# MCU.net
KiCad netlist of a schematic drawn in Altium Designer
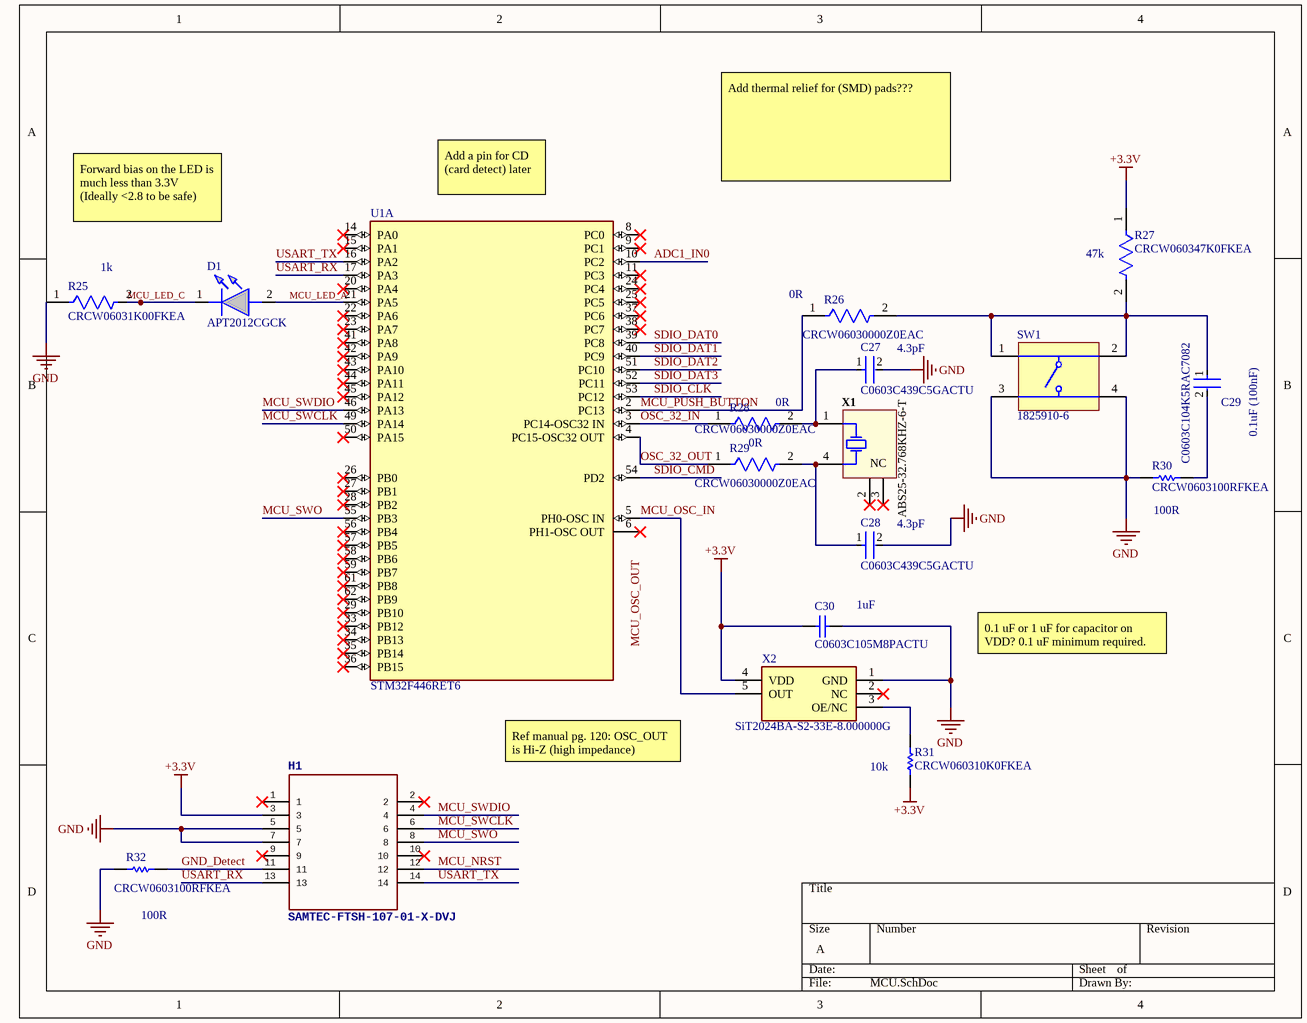
[diagram p0: MCU.SchDoc]

(export (version "E")
  (design (tool "Eeschema 10.0.6"))
  (components
    (comp (ref "C27")
      (value "C0603C439C5GACTU")
      (footprint "FP-C0603C-CF-MFG")
      (description "CAP CER 4.3PF 50V NP0 0603")
      (fields
        (field (name "OCTOPART") "https://octopart.com/c0603c439c5gactu-kemet-8375741")
        (field (name "TOLERANCE") "0.25 pF")
      )
      (libsource (lib "Altium Content Vault") (part "b4654b650e69147ec39a6b967a45e02"))
    )
    (comp (ref "C28")
      (value "C0603C439C5GACTU")
      (footprint "FP-C0603C-CF-MFG")
      (description "CAP CER 4.3PF 50V NP0 0603")
      (fields
        (field (name "OCTOPART") "https://octopart.com/c0603c439c5gactu-kemet-8375741")
        (field (name "TOLERANCE") "0.25 pF")
      )
      (libsource (lib "Altium Content Vault") (part "b4654b650e69147ec39a6b967a45e02"))
    )
    (comp (ref "C29")
      (value "C0603C104K5RAC7082")
      (footprint "FP-C0603C-CF-MFG")
      (description "C0603 0.10 μF X7R 30ppm/°C 10.00% 50 V")
      (fields
        (field (name "OCTOPART") "https://octopart.com/c0603c104k5rac7082-kemet-75146597")
        (field (name "MANUFACTURER") "KEMET")
      )
      (libsource (lib "Altium Content Vault") (part "b4654b650e69147ec39a6b967a45e02"))
    )
    (comp (ref "C30")
      (value "C0603C105M8PACTU")
      (footprint "CAPC1608X90X35LL15T15")
      (fields (field (name "MANUFACTURER") "Kemet"))
      (libsource (lib "Altium Content Vault") (part "CAP"))
    )
    (comp (ref "D1")
      (value "APT2012CGCK")
      (footprint "LEDC2012X50N")
      (fields (field (name "MOUSER PART NUMBER") "604-APT2012CGCK"))
      (libsource (lib "APT2012CGCK") (part "APT2012CGCK"))
    )
    (comp (ref "H1")
      (value "SAMTEC-FTSH-107-01-X-DVJ")
      (footprint "SAMTEC_FTSH-107-01-F-DV-K-P-TR")
      (libsource (lib "SAMTEC-FTSH-107-01-X-DV") (part "SAMTEC-FTSH-107-01-X-DVJ"))
    )
    (comp (ref "R25")
      (value "CRCW06031K00FKEA")
      (footprint "FP-CRCW0603-e3-MFG")
      (description "RES Thick Film, 1kΩ, 1%, 0.1W, 100ppm/°C, 0603")
      (fields (field (name "TOLERANCE") "1%"))
      (libsource (lib "Altium Content Vault") (part "1029c3af85768c4190bb7ad29bc67b5"))
    )
    (comp (ref "R26")
      (value "CRCW06030000Z0EAC")
      (footprint "FP-CRCW0603-C-IPC_B")
      (description "RES 0 OHM JUMPER 1/10W 0603")
      (libsource (lib "Altium Content Vault") (part "1029c3af85768c4190bb7ad29bc67b5"))
    )
    (comp (ref "R27")
      (value "CRCW060347K0FKEA")
      (footprint "FP-CRCW0603-e3-IPC_B")
      (description "RES SMD 47K OHM 1% 1/10W 0603")
      (fields (field (name "TOLERANCE") "1%"))
      (libsource (lib "Altium Content Vault") (part "1029c3af85768c4190bb7ad29bc67b5"))
    )
    (comp (ref "R28")
      (value "CRCW06030000Z0EAC")
      (footprint "FP-CRCW0603-C-IPC_B")
      (description "RES 0 OHM JUMPER 1/10W 0603")
      (libsource (lib "Altium Content Vault") (part "1029c3af85768c4190bb7ad29bc67b5"))
    )
    (comp (ref "R29")
      (value "CRCW06030000Z0EAC")
      (footprint "FP-CRCW0603-C-IPC_B")
      (description "RES 0 OHM JUMPER 1/10W 0603")
      (libsource (lib "Altium Content Vault") (part "1029c3af85768c4190bb7ad29bc67b5"))
    )
    (comp (ref "R30")
      (value "CRCW0603100RFKEA")
      (footprint "RESC1609X50X30ML8T20")
      (description "Chip Resistor, 100 Ohm, +/- 1%, 100 mW,-55 to 155 degC, 0603 (1608 Metric), RoHS, Tape and Ree")
      (fields (field (name "MANUFACTURER") "Vishay Semiconductor"))
      (libsource (lib "Altium Content Vault") (part "RES-2"))
    )
    (comp (ref "R31")
      (value "CRCW060310K0FKEA")
      (footprint "RESC1609X50X30NL8T20")
      (description "Chip Resistor, 10 KOhm, +/- 1%, 100 mW, -55 to 155 degC, 0603 (1608 Metric), RoHS, Tape and Reel")
      (fields (field (name "MANUFACTURER") "Vishay Semiconductor"))
      (libsource (lib "Altium Content Vault") (part "RES-2"))
    )
    (comp (ref "R32")
      (value "CRCW0603100RFKEA")
      (footprint "RESC1609X50X30ML8T20")
      (description "Chip Resistor, 100 Ohm, +/- 1%, 100 mW,-55 to 155 degC, 0603 (1608 Metric), RoHS, Tape and Ree")
      (fields (field (name "MANUFACTURER") "Vishay Semiconductor"))
      (libsource (lib "Altium Content Vault") (part "RES-2"))
    )
    (comp (ref "SW1")
      (value "1825910-6")
      (footprint "TECO-1825910-6_V")
      (description "Tact Switch, SPST-NO, 0.05 A, -35 to 85 degC, 4-Pin THD, RoHS, Bulk")
      (fields (field (name "MANUFACTURER") "TE Connectivity"))
      (libsource (lib "Altium Content Vault") (part "SW-SPST-4_A"))
    )
    (comp (ref "U1")
      (value "STM32F446RET6")
      (footprint "FP-LQFP64-5W-MFG")
      (description "IC MCU 32BIT 512KB FLASH 64LQFP")
      (fields
        (field (name "OCTOPART") "https://octopart.com/stm32f446ret6-stmicroelectronics-52642920")
        (field (name "MANUFACTURER") "ST")
      )
      (libsource (lib "Altium Content Vault") (part "ee11adc32c0ab33b933cccf4348c338"))
    )
    (comp (ref "X1")
      (value "ABS25-32.768KHZ-6-T")
      (footprint "ABRA-ABS25-4_V")
      (fields (field (name "TOLERANCE") "20PPM") (field (name "MANUFACTURER") "Abracon"))
      (libsource (lib "Altium Content Vault") (part "ABRA-XTAL_1-4-4"))
    )
    (comp (ref "X2")
      (value "SiT2024BA-S2-33E-8.000000G")
      (footprint "SOT95P280X145-5N")
      (description "Standard Clock Oscillators 8MHz 3.3V -40C +125C AEC-Q100")
      (fields (field (name "MOUSER PART NUMBER") "788-2024BA-S2-33E-8G"))
      (libsource (lib "SiT2024BA-S2-33E-8.000000G") (part "SiT2024BA-S2-33E-8.000000G"))
    )
  )
  (nets
    (net (code "1") (name "+3.3V") (class "Default")
      (node (ref "C30") (pin "1") (pinfunction "1_1") (pintype "passive"))
      (node (ref "H1") (pin "3") (pinfunction "3_3") (pintype "passive"))
      (node (ref "R27") (pin "1") (pinfunction "1_1") (pintype "passive"))
      (node (ref "R31") (pin "2") (pinfunction "2_2") (pintype "passive"))
      (node (ref "X2") (pin "4") (pinfunction "VDD_4") (pintype "power_in"))
    )
    (net (code "2") (name "/ADC1_IN0") (class "Default")
      (node (ref "U1") (pin "10") (pinfunction "PC2_10") (pintype "bidirectional"))
    )
    (net (code "3") (name "/GND_Detect") (class "Default")
      (node (ref "H1") (pin "11") (pinfunction "11_11") (pintype "passive"))
      (node (ref "R32") (pin "1") (pinfunction "1_1") (pintype "passive"))
    )
    (net (code "4") (name "/MCU_LED_A") (class "Default")
      (node (ref "D1") (pin "2") (pinfunction "A_2") (pintype "passive"))
      (node (ref "U1") (pin "21") (pinfunction "PA5_21") (pintype "bidirectional"))
    )
    (net (code "5") (name "/MCU_LED_C") (class "Default")
      (node (ref "D1") (pin "1") (pinfunction "K_1") (pintype "passive"))
      (node (ref "R25") (pin "2") (pinfunction "2_2") (pintype "passive"))
    )
    (net (code "6") (name "/MCU_NRST") (class "Default")
      (node (ref "H1") (pin "12") (pinfunction "12_12") (pintype "passive"))
    )
    (net (code "7") (name "/MCU_OSC_IN") (class "Default")
      (node (ref "U1") (pin "5") (pinfunction "PH0-OSC_IN_5") (pintype "bidirectional"))
      (node (ref "X2") (pin "5") (pinfunction "OUT_5") (pintype "passive"))
    )
    (net (code "9") (name "/MCU_PUSH_BUTTON") (class "Default")
      (node (ref "R26") (pin "1") (pinfunction "1_1") (pintype "passive"))
      (node (ref "U1") (pin "2") (pinfunction "PC13_2") (pintype "bidirectional"))
    )
    (net (code "10") (name "/MCU_SWCLK") (class "Default")
      (node (ref "H1") (pin "6") (pinfunction "6_6") (pintype "passive"))
      (node (ref "U1") (pin "49") (pinfunction "PA14_49") (pintype "bidirectional"))
    )
    (net (code "11") (name "/MCU_SWDIO") (class "Default")
      (node (ref "H1") (pin "4") (pinfunction "4_4") (pintype "passive"))
      (node (ref "U1") (pin "46") (pinfunction "PA13_46") (pintype "bidirectional"))
    )
    (net (code "12") (name "/MCU_SWO") (class "Default")
      (node (ref "H1") (pin "8") (pinfunction "8_8") (pintype "passive"))
      (node (ref "U1") (pin "55") (pinfunction "PB3_55") (pintype "bidirectional"))
    )
    (net (code "13") (name "/OSC_32_IN") (class "Default")
      (node (ref "R28") (pin "1") (pinfunction "1_1") (pintype "passive"))
      (node (ref "U1") (pin "3") (pinfunction "PC14-OSC32_IN_3") (pintype "bidirectional"))
    )
    (net (code "14") (name "/OSC_32_OUT") (class "Default")
      (node (ref "R29") (pin "1") (pinfunction "1_1") (pintype "passive"))
      (node (ref "U1") (pin "4") (pinfunction "PC15-OSC32_OUT_4") (pintype "bidirectional"))
    )
    (net (code "15") (name "/SDIO_CLK") (class "Default")
      (node (ref "U1") (pin "53") (pinfunction "PC12_53") (pintype "bidirectional"))
    )
    (net (code "16") (name "/SDIO_CMD") (class "Default")
      (node (ref "U1") (pin "54") (pinfunction "PD2_54") (pintype "bidirectional"))
    )
    (net (code "17") (name "/SDIO_DAT0") (class "Default")
      (node (ref "U1") (pin "39") (pinfunction "PC8_39") (pintype "bidirectional"))
    )
    (net (code "18") (name "/SDIO_DAT1") (class "Default")
      (node (ref "U1") (pin "40") (pinfunction "PC9_40") (pintype "bidirectional"))
    )
    (net (code "19") (name "/SDIO_DAT2") (class "Default")
      (node (ref "U1") (pin "51") (pinfunction "PC10_51") (pintype "bidirectional"))
    )
    (net (code "20") (name "/SDIO_DAT3") (class "Default")
      (node (ref "U1") (pin "52") (pinfunction "PC11_52") (pintype "bidirectional"))
    )
    (net (code "21") (name "/USART_RX") (class "Default")
      (node (ref "H1") (pin "13") (pinfunction "13_13") (pintype "passive"))
      (node (ref "U1") (pin "17") (pinfunction "PA3_17") (pintype "bidirectional"))
    )
    (net (code "22") (name "/USART_TX") (class "Default")
      (node (ref "H1") (pin "14") (pinfunction "14_14") (pintype "passive"))
      (node (ref "U1") (pin "16") (pinfunction "PA2_16") (pintype "bidirectional"))
    )
    (net (code "23") (name "GND") (class "Default")
      (node (ref "C27") (pin "2") (pinfunction "2_2") (pintype "passive"))
      (node (ref "C28") (pin "2") (pinfunction "2_2") (pintype "passive"))
      (node (ref "C30") (pin "2") (pinfunction "2_2") (pintype "passive"))
      (node (ref "H1") (pin "5") (pinfunction "5_5") (pintype "passive"))
      (node (ref "H1") (pin "7") (pinfunction "7_7") (pintype "passive"))
      (node (ref "R25") (pin "1") (pinfunction "1_1") (pintype "passive"))
      (node (ref "R30") (pin "2") (pinfunction "2_2") (pintype "passive"))
      (node (ref "R32") (pin "2") (pinfunction "2_2") (pintype "passive"))
      (node (ref "SW1") (pin "3") (pinfunction "3_3") (pintype "passive"))
      (node (ref "SW1") (pin "4") (pinfunction "4_4") (pintype "passive"))
      (node (ref "X2") (pin "1") (pinfunction "GND_1") (pintype "passive"))
    )
    (net (code "24") (name "Net-(C29-Pad1)") (class "Default")
      (node (ref "C29") (pin "1") (pinfunction "1_1") (pintype "passive"))
      (node (ref "R26") (pin "2") (pinfunction "2_2") (pintype "passive"))
      (node (ref "R27") (pin "2") (pinfunction "2_2") (pintype "passive"))
      (node (ref "SW1") (pin "1") (pinfunction "1_1") (pintype "passive"))
      (node (ref "SW1") (pin "2") (pinfunction "2_2") (pintype "passive"))
    )
    (net (code "25") (name "Net-(C29-Pad2)") (class "Default")
      (node (ref "C29") (pin "2") (pinfunction "2_2") (pintype "passive"))
      (node (ref "R30") (pin "1") (pinfunction "1_1") (pintype "passive"))
    )
    (net (code "26") (name "Net-(X1-X1)") (class "Default")
      (node (ref "C27") (pin "1") (pinfunction "1_1") (pintype "passive"))
      (node (ref "R28") (pin "2") (pinfunction "2_2") (pintype "passive"))
      (node (ref "X1") (pin "1") (pinfunction "X1_1") (pintype "passive"))
    )
    (net (code "27") (name "Net-(X1-X2)") (class "Default")
      (node (ref "C28") (pin "1") (pinfunction "1_1") (pintype "passive"))
      (node (ref "R29") (pin "2") (pinfunction "2_2") (pintype "passive"))
      (node (ref "X1") (pin "4") (pinfunction "X2_4") (pintype "passive"))
    )
    (net (code "28") (name "Net-(X2-OE{slash}NC)") (class "Default")
      (node (ref "R31") (pin "1") (pinfunction "1_1") (pintype "passive"))
      (node (ref "X2") (pin "3") (pinfunction "OE/NC_3") (pintype "passive"))
    )
    (net (code "29") (name "unconnected-(H1-Pad1)") (class "Default")
      (node (ref "H1") (pin "1") (pinfunction "1_1") (pintype "passive+no_connect"))
    )
    (net (code "30") (name "unconnected-(H1-Pad2)") (class "Default")
      (node (ref "H1") (pin "2") (pinfunction "2_2") (pintype "passive+no_connect"))
    )
    (net (code "31") (name "unconnected-(H1-Pad9)") (class "Default")
      (node (ref "H1") (pin "9") (pinfunction "9_9") (pintype "passive+no_connect"))
    )
    (net (code "32") (name "unconnected-(H1-Pad10)") (class "Default")
      (node (ref "H1") (pin "10") (pinfunction "10_10") (pintype "passive+no_connect"))
    )
    (net (code "33") (name "unconnected-(U1A-PA0-Pad14)") (class "Default")
      (node (ref "U1") (pin "14") (pinfunction "PA0_14") (pintype "bidirectional+no_connect"))
    )
    (net (code "34") (name "unconnected-(U1A-PA1-Pad15)") (class "Default")
      (node (ref "U1") (pin "15") (pinfunction "PA1_15") (pintype "bidirectional+no_connect"))
    )
    (net (code "35") (name "unconnected-(U1A-PA4-Pad20)") (class "Default")
      (node (ref "U1") (pin "20") (pinfunction "PA4_20") (pintype "bidirectional+no_connect"))
    )
    (net (code "36") (name "unconnected-(U1A-PA6-Pad22)") (class "Default")
      (node (ref "U1") (pin "22") (pinfunction "PA6_22") (pintype "bidirectional+no_connect"))
    )
    (net (code "37") (name "unconnected-(U1A-PA7-Pad23)") (class "Default")
      (node (ref "U1") (pin "23") (pinfunction "PA7_23") (pintype "bidirectional+no_connect"))
    )
    (net (code "38") (name "unconnected-(U1A-PA8-Pad41)") (class "Default")
      (node (ref "U1") (pin "41") (pinfunction "PA8_41") (pintype "bidirectional+no_connect"))
    )
    (net (code "39") (name "unconnected-(U1A-PA9-Pad42)") (class "Default")
      (node (ref "U1") (pin "42") (pinfunction "PA9_42") (pintype "bidirectional+no_connect"))
    )
    (net (code "40") (name "unconnected-(U1A-PA10-Pad43)") (class "Default")
      (node (ref "U1") (pin "43") (pinfunction "PA10_43") (pintype "bidirectional+no_connect"))
    )
    (net (code "41") (name "unconnected-(U1A-PA11-Pad44)") (class "Default")
      (node (ref "U1") (pin "44") (pinfunction "PA11_44") (pintype "bidirectional+no_connect"))
    )
    (net (code "42") (name "unconnected-(U1A-PA12-Pad45)") (class "Default")
      (node (ref "U1") (pin "45") (pinfunction "PA12_45") (pintype "bidirectional+no_connect"))
    )
    (net (code "43") (name "unconnected-(U1A-PA15-Pad50)") (class "Default")
      (node (ref "U1") (pin "50") (pinfunction "PA15_50") (pintype "bidirectional+no_connect"))
    )
    (net (code "44") (name "unconnected-(U1A-PB0-Pad26)") (class "Default")
      (node (ref "U1") (pin "26") (pinfunction "PB0_26") (pintype "bidirectional+no_connect"))
    )
    (net (code "45") (name "unconnected-(U1A-PB1-Pad27)") (class "Default")
      (node (ref "U1") (pin "27") (pinfunction "PB1_27") (pintype "bidirectional+no_connect"))
    )
    (net (code "46") (name "unconnected-(U1A-PB2-Pad28)") (class "Default")
      (node (ref "U1") (pin "28") (pinfunction "PB2_28") (pintype "bidirectional+no_connect"))
    )
    (net (code "47") (name "unconnected-(U1A-PB4-Pad56)") (class "Default")
      (node (ref "U1") (pin "56") (pinfunction "PB4_56") (pintype "bidirectional+no_connect"))
    )
    (net (code "48") (name "unconnected-(U1A-PB5-Pad57)") (class "Default")
      (node (ref "U1") (pin "57") (pinfunction "PB5_57") (pintype "bidirectional+no_connect"))
    )
    (net (code "49") (name "unconnected-(U1A-PB6-Pad58)") (class "Default")
      (node (ref "U1") (pin "58") (pinfunction "PB6_58") (pintype "bidirectional+no_connect"))
    )
    (net (code "50") (name "unconnected-(U1A-PB7-Pad59)") (class "Default")
      (node (ref "U1") (pin "59") (pinfunction "PB7_59") (pintype "bidirectional+no_connect"))
    )
    (net (code "51") (name "unconnected-(U1A-PB8-Pad61)") (class "Default")
      (node (ref "U1") (pin "61") (pinfunction "PB8_61") (pintype "bidirectional+no_connect"))
    )
    (net (code "52") (name "unconnected-(U1A-PB9-Pad62)") (class "Default")
      (node (ref "U1") (pin "62") (pinfunction "PB9_62") (pintype "bidirectional+no_connect"))
    )
    (net (code "53") (name "unconnected-(U1A-PB10-Pad29)") (class "Default")
      (node (ref "U1") (pin "29") (pinfunction "PB10_29") (pintype "bidirectional+no_connect"))
    )
    (net (code "54") (name "unconnected-(U1A-PB12-Pad33)") (class "Default")
      (node (ref "U1") (pin "33") (pinfunction "PB12_33") (pintype "bidirectional+no_connect"))
    )
    (net (code "55") (name "unconnected-(U1A-PB13-Pad34)") (class "Default")
      (node (ref "U1") (pin "34") (pinfunction "PB13_34") (pintype "bidirectional+no_connect"))
    )
    (net (code "56") (name "unconnected-(U1A-PB14-Pad35)") (class "Default")
      (node (ref "U1") (pin "35") (pinfunction "PB14_35") (pintype "bidirectional+no_connect"))
    )
    (net (code "57") (name "unconnected-(U1A-PB15-Pad36)") (class "Default")
      (node (ref "U1") (pin "36") (pinfunction "PB15_36") (pintype "bidirectional+no_connect"))
    )
    (net (code "58") (name "unconnected-(U1A-PC0-Pad8)") (class "Default")
      (node (ref "U1") (pin "8") (pinfunction "PC0_8") (pintype "bidirectional+no_connect"))
    )
    (net (code "59") (name "unconnected-(U1A-PC1-Pad9)") (class "Default")
      (node (ref "U1") (pin "9") (pinfunction "PC1_9") (pintype "bidirectional+no_connect"))
    )
    (net (code "60") (name "unconnected-(U1A-PC3-Pad11)") (class "Default")
      (node (ref "U1") (pin "11") (pinfunction "PC3_11") (pintype "bidirectional+no_connect"))
    )
    (net (code "61") (name "unconnected-(U1A-PC4-Pad24)") (class "Default")
      (node (ref "U1") (pin "24") (pinfunction "PC4_24") (pintype "bidirectional+no_connect"))
    )
    (net (code "62") (name "unconnected-(U1A-PC5-Pad25)") (class "Default")
      (node (ref "U1") (pin "25") (pinfunction "PC5_25") (pintype "bidirectional+no_connect"))
    )
    (net (code "63") (name "unconnected-(U1A-PC6-Pad37)") (class "Default")
      (node (ref "U1") (pin "37") (pinfunction "PC6_37") (pintype "bidirectional+no_connect"))
    )
    (net (code "64") (name "unconnected-(U1A-PC7-Pad38)") (class "Default")
      (node (ref "U1") (pin "38") (pinfunction "PC7_38") (pintype "bidirectional+no_connect"))
    )
    (net (code "65") (name "unconnected-(U1A-PH1-OSC_OUT-Pad6)") (class "Default")
      (node (ref "U1") (pin "6") (pinfunction "PH1-OSC_OUT_6") (pintype "tri_state+no_connect"))
    )
    (net (code "66") (name "unconnected-(X1-NC-Pad2)") (class "Default")
      (node (ref "X1") (pin "2") (pinfunction "NC_2") (pintype "passive+no_connect"))
    )
    (net (code "67") (name "unconnected-(X1-NC-Pad3)") (class "Default")
      (node (ref "X1") (pin "3") (pinfunction "NC_3") (pintype "passive+no_connect"))
    )
    (net (code "68") (name "unconnected-(X2-NC-Pad2)") (class "Default")
      (node (ref "X2") (pin "2") (pinfunction "NC_2") (pintype "passive+no_connect"))
    )
  )
)
